# i2c0.net
KiCad netlist of a schematic drawn in Altium Designer
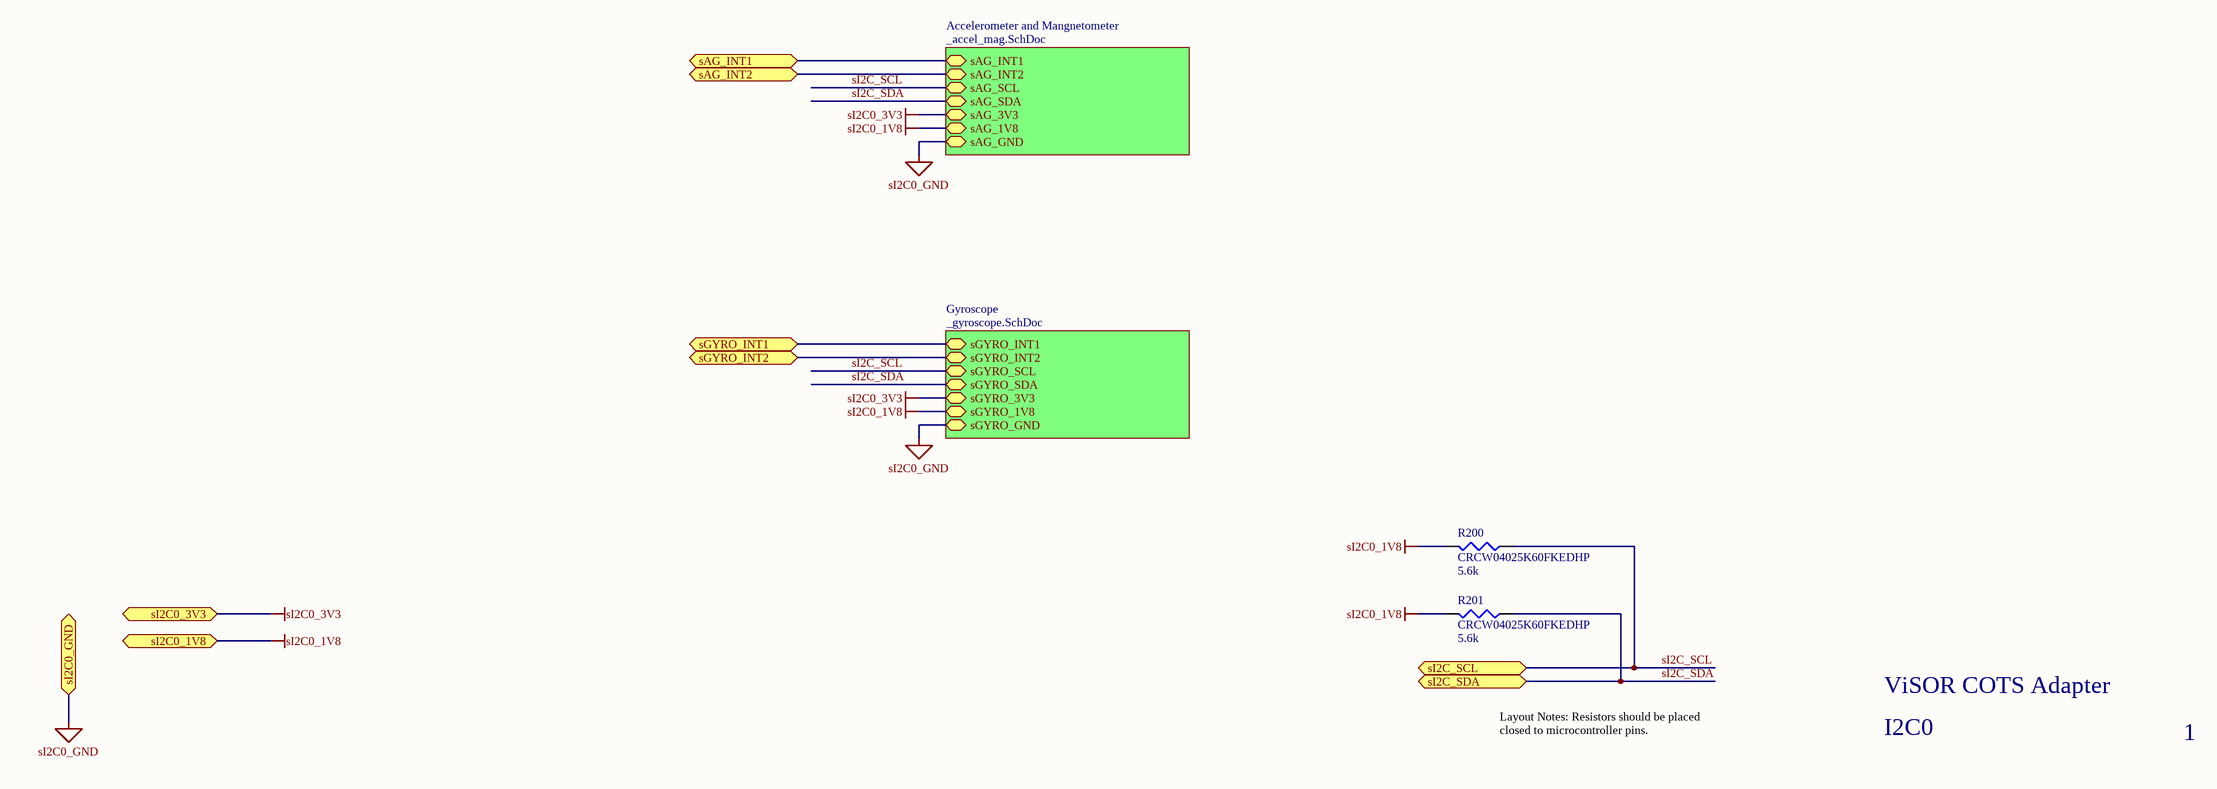
[diagram p0: _i2c0.SchDoc]

(export (version "E")
  (design (tool "Eeschema 10.0.6"))
  (components
    (comp (ref "R200")
      (value "CRCW04025K60FKEDHP")
      (footprint "0402")
      (description "0.125W, -55-155C, 1005, 50V, ±1%")
      (fields (field (name "ALTIUM_VALUE") "5.6k"))
      (libsource (lib "standard_resistors") (part "CRCW0402xxxxFKED"))
    )
    (comp (ref "R201")
      (value "CRCW04025K60FKEDHP")
      (footprint "0402")
      (description "0.125W, -55-155C, 1005, 50V, ±1%")
      (fields (field (name "ALTIUM_VALUE") "5.6k"))
      (libsource (lib "standard_resistors") (part "CRCW0402xxxxFKED"))
    )
  )
  (nets
    (net (code "5") (name "/sI2C_SCL") (class "Default")
      (node (ref "R200") (pin "1") (pinfunction "1_1") (pintype "passive"))
    )
    (net (code "6") (name "/sI2C_SDA") (class "Default")
      (node (ref "R201") (pin "1") (pinfunction "1_1") (pintype "passive"))
    )
    (net (code "7") (name "sI2C0_1V8") (class "Default")
      (node (ref "R200") (pin "2") (pinfunction "2_2") (pintype "passive"))
      (node (ref "R201") (pin "2") (pinfunction "2_2") (pintype "passive"))
    )
  )
)
